# PSU_LP385_ADJ1.net
KiCad netlist of a schematic drawn in Altium Designer
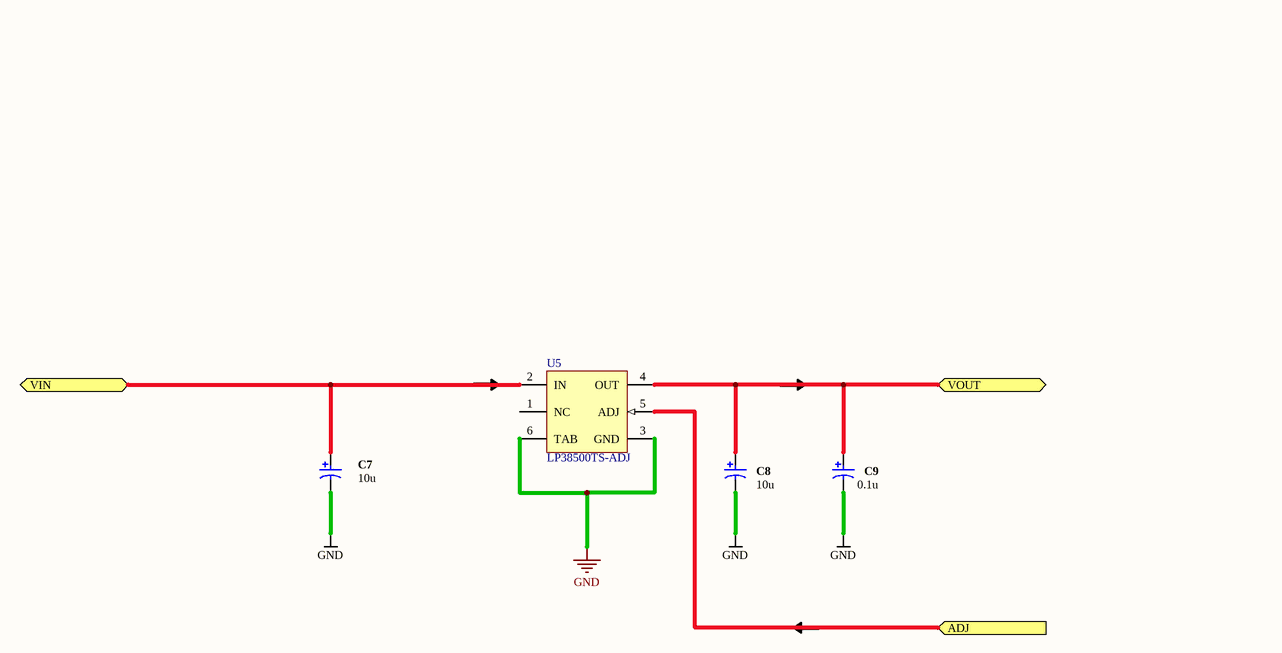
[diagram p0: PSU_LP385_ADJ1.SchDoc]

(export (version "E")
  (design (tool "Eeschema 10.0.6"))
  (components
    (comp (ref "C7")
      (value "10u")
      (footprint "CAPC3528-STAR")
      (description "Capacitor, Tantalum, 10uF 10% 20V MCCT-B (3528)")
      (fields (field (name "TOLERANCE") "10 %"))
      (libsource (lib "altium-import") (part "root_0_CAP-P_"))
    )
    (comp (ref "C8")
      (value "10u")
      (footprint "CAPC3528-STAR")
      (description "Capacitor, Tantalum, 10uF 10% 20V MCCT-B (3528)")
      (fields (field (name "TOLERANCE") "10 %"))
      (libsource (lib "altium-import") (part "root_0_CAP-P_"))
    )
    (comp (ref "C9")
      (value "0.1u")
      (footprint "CAPC7343-STAR")
      (description "Capacitor, Tantalum, 220uF 10% 10V MCCT-D (7343-31)")
      (fields (field (name "TOLERANCE") "10 %"))
      (libsource (lib "altium-import") (part "root_0_CAP-P_"))
    )
    (comp (ref "U5")
      (value "LP38500TS-ADJ")
      (footprint "TS5B_M")
      (description "1.5A FlexCap Low Dropout Linear Regulator for 2.7V to 5.5V Inputs, 5-pin TO-263")
      (fields (field (name "MANUFACTURER") "National Semiconductor"))
      (libsource (lib "National Semiconductor LDO") (part "LP38500TS-ADJ"))
    )
  )
  (nets
    (net (code "1") (name "/ADJ") (class "Default")
      (node (ref "U5") (pin "5") (pinfunction "ADJ_5") (pintype "input"))
    )
    (net (code "2") (name "/VIN") (class "Default")
      (node (ref "C7") (pin "1") (pinfunction "1_1") (pintype "passive"))
      (node (ref "U5") (pin "2") (pinfunction "IN_2") (pintype "power_in"))
    )
    (net (code "3") (name "/VOUT") (class "Default")
      (node (ref "C8") (pin "1") (pinfunction "1_1") (pintype "passive"))
      (node (ref "C9") (pin "1") (pinfunction "1_1") (pintype "passive"))
      (node (ref "U5") (pin "4") (pinfunction "OUT_4") (pintype "power_in"))
    )
    (net (code "4") (name "GND") (class "Default")
      (node (ref "C7") (pin "2") (pinfunction "2_2") (pintype "passive"))
      (node (ref "C8") (pin "2") (pinfunction "2_2") (pintype "passive"))
      (node (ref "C9") (pin "2") (pinfunction "2_2") (pintype "passive"))
      (node (ref "U5") (pin "3") (pinfunction "GND_3") (pintype "power_in"))
      (node (ref "U5") (pin "6") (pinfunction "TAB_6") (pintype "power_in"))
    )
    (net (code "5") (name "unconnected-(U5-NC-Pad1)") (class "Default")
      (node (ref "U5") (pin "1") (pinfunction "NC_1") (pintype "passive"))
    )
  )
)
